# 5VCircuit.net
KiCad netlist of a schematic drawn in Altium Designer
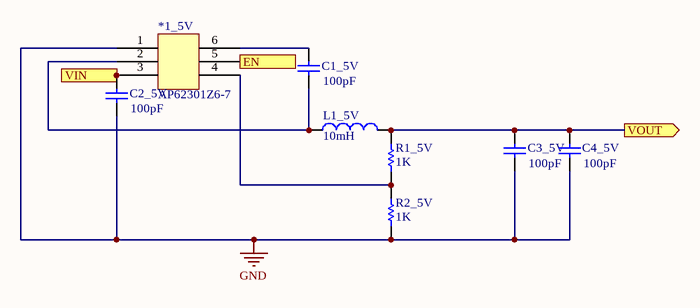
[diagram p0: 5VCircuit.SchDoc]

(export (version "E")
  (design (tool "Eeschema 10.0.6"))
  (components
    (comp (ref "*1_5V")
      (value "AP62301Z6-7")
      (footprint "SOT-563-6")
      (description "Switching Voltage Regulators DCDC Conv HV Buck SOT563 T&R 3K")
      (libsource (lib "Lib") (part "AP62301Z6-7"))
    )
    (comp (ref "C1_5V")
      (value "100pF")
      (footprint "1608[0603]")
      (description "Capacitor")
      (fields (field (name "Comment") "Cap") (field (name "PUBLISHER") "Altium Limited"))
      (libsource (lib "Miscellaneous Devices") (part "Cap"))
    )
    (comp (ref "C2_5V")
      (value "100pF")
      (footprint "1608[0603]")
      (description "Capacitor")
      (fields (field (name "Comment") "Cap") (field (name "PUBLISHER") "Altium Limited"))
      (libsource (lib "Miscellaneous Devices") (part "Cap"))
    )
    (comp (ref "C3_5V")
      (value "100pF")
      (footprint "1608[0603]")
      (description "Capacitor")
      (fields (field (name "Comment") "Cap") (field (name "PUBLISHER") "Altium Limited"))
      (libsource (lib "Miscellaneous Devices") (part "Cap"))
    )
    (comp (ref "C4_5V")
      (value "100pF")
      (footprint "1608[0603]")
      (description "Capacitor")
      (fields (field (name "Comment") "Cap") (field (name "PUBLISHER") "Altium Limited"))
      (libsource (lib "Miscellaneous Devices") (part "Cap"))
    )
    (comp (ref "L1_5V")
      (value "10mH")
      (footprint "0402-A")
      (description "Inductor")
      (fields (field (name "PUBLISHER") "Altium Limited"))
      (libsource (lib "Miscellaneous Devices") (part "Inductor"))
    )
    (comp (ref "R1_5V")
      (value "1K")
      (footprint "1608[0603]")
      (description "Resistor")
      (fields (field (name "Comment") "Res1") (field (name "PUBLISHER") "Altium Limited"))
      (libsource (lib "Miscellaneous Devices") (part "Res1"))
    )
    (comp (ref "R2_5V")
      (value "1K")
      (footprint "1608[0603]")
      (description "Resistor")
      (fields (field (name "Comment") "Res1") (field (name "PUBLISHER") "Altium Limited"))
      (libsource (lib "Miscellaneous Devices") (part "Res1"))
    )
  )
  (nets
    (net (code "1") (name "/EN") (class "Default") (node (ref "*1_5V") (pin "5") (pintype "passive")))
    (net (code "2") (name "/VIN") (class "Default")
      (node (ref "*1_5V") (pin "3") (pintype "passive"))
      (node (ref "C2_5V") (pin "2") (pinfunction "2_2") (pintype "passive"))
    )
    (net (code "3") (name "/VOUT") (class "Default")
      (node (ref "C3_5V") (pin "2") (pinfunction "2_2") (pintype "passive"))
      (node (ref "C4_5V") (pin "2") (pinfunction "2_2") (pintype "passive"))
      (node (ref "L1_5V") (pin "2") (pinfunction "2_2") (pintype "passive"))
      (node (ref "R1_5V") (pin "1") (pinfunction "1_1") (pintype "passive"))
    )
    (net (code "4") (name "GND") (class "Default")
      (node (ref "*1_5V") (pin "1") (pintype "passive"))
      (node (ref "C2_5V") (pin "1") (pinfunction "1_1") (pintype "passive"))
      (node (ref "C3_5V") (pin "1") (pinfunction "1_1") (pintype "passive"))
      (node (ref "C4_5V") (pin "1") (pinfunction "1_1") (pintype "passive"))
      (node (ref "R2_5V") (pin "2") (pinfunction "2_2") (pintype "passive"))
    )
    (net (code "5") (name "Net-(*1_5V-Pad2)") (class "Default")
      (node (ref "*1_5V") (pin "2") (pintype "passive"))
      (node (ref "C1_5V") (pin "1") (pinfunction "1_1") (pintype "passive"))
      (node (ref "L1_5V") (pin "1") (pinfunction "1_1") (pintype "passive"))
    )
    (net (code "6") (name "Net-(*1_5V-Pad4)") (class "Default")
      (node (ref "*1_5V") (pin "4") (pintype "passive"))
      (node (ref "R1_5V") (pin "2") (pinfunction "2_2") (pintype "passive"))
      (node (ref "R2_5V") (pin "1") (pinfunction "1_1") (pintype "passive"))
    )
    (net (code "7") (name "Net-(*1_5V-Pad6)") (class "Default")
      (node (ref "*1_5V") (pin "6") (pintype "passive"))
      (node (ref "C1_5V") (pin "2") (pinfunction "2_2") (pintype "passive"))
    )
  )
)
